# PowerDriver.net
KiCad netlist of a schematic drawn in Altium Designer
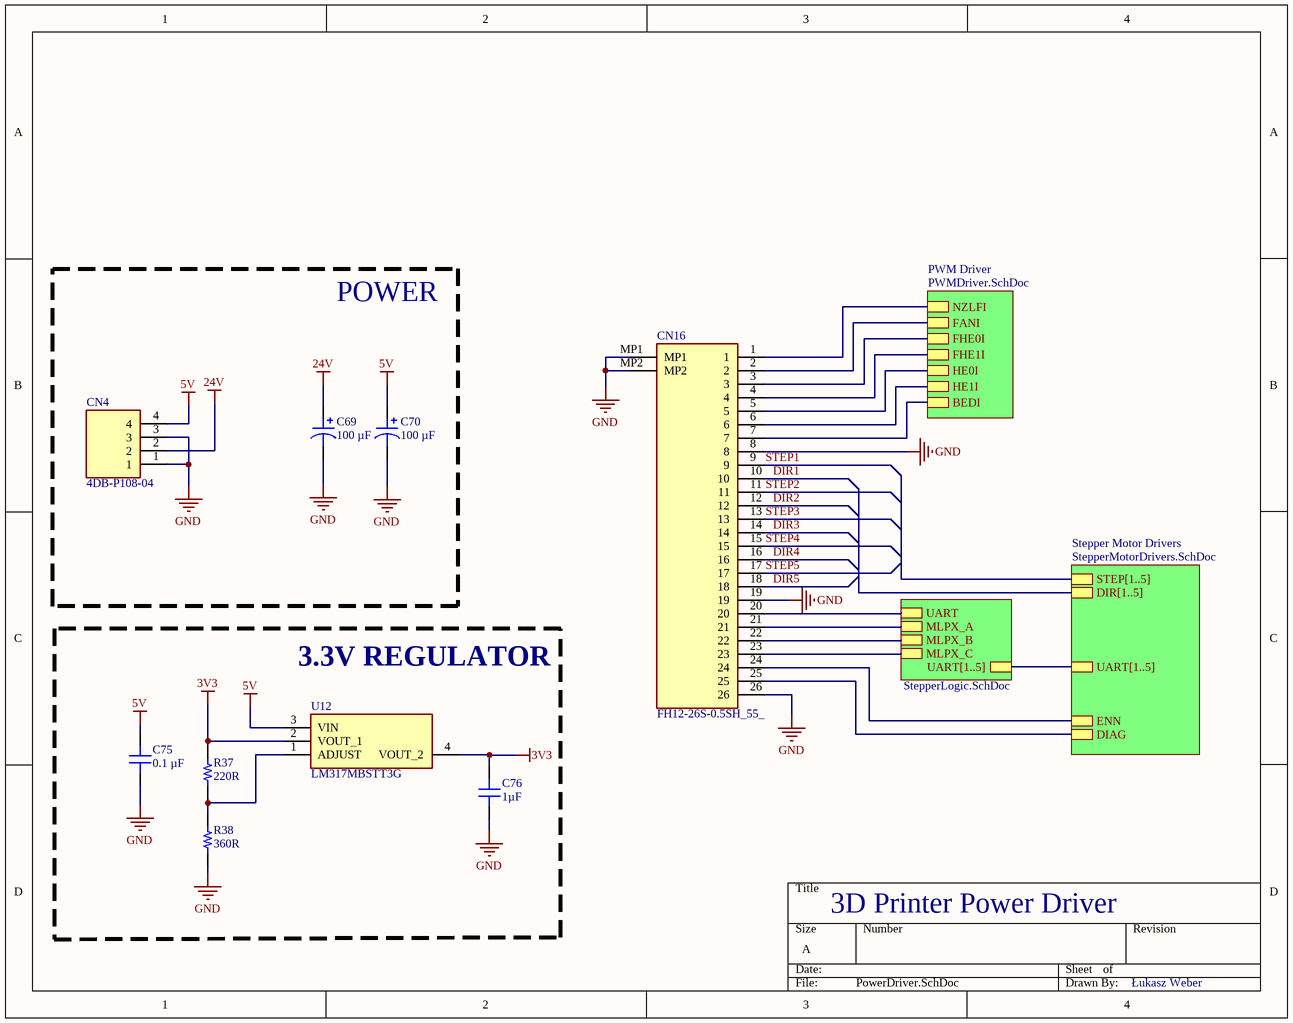
[diagram p0: PowerDriver.SchDoc]

(export (version "E")
  (design (tool "Eeschema 10.0.6"))
  (components
    (comp (ref "C69")
      (value "100 µF")
      (footprint "CAP ALSMD 6.6MM H7.7MM")
      (description "CAP ALUM 100UF 20% 25V SMD")
      (fields (field (name "PART NUMBER") "UWT1E101MCL1GS") (field (name "MANUFACTURER") "Nichicon"))
      (libsource (lib "Celestial Altium Library - altium_library") (part "Polarised Capacitor"))
    )
    (comp (ref "C70")
      (value "100 µF")
      (footprint "CAP ALSMD 6.6MM H7.7MM")
      (description "CAP ALUM 100UF 20% 25V SMD")
      (fields (field (name "PART NUMBER") "UWT1E101MCL1GS") (field (name "MANUFACTURER") "Nichicon"))
      (libsource (lib "Celestial Altium Library - altium_library") (part "Polarised Capacitor"))
    )
    (comp (ref "C75")
      (value "0.1 µF")
      (footprint "CAP 0603_1608")
      (description "CAP CER 0.1UF 100V X7R 0603")
      (fields
        (field (name "PART NUMBER") "0603B104K101CT")
        (field (name "MANUFACTURER") "Walsin Technology Corporation")
      )
      (libsource (lib "Celestial Altium Library - altium_library") (part "Capacitor"))
    )
    (comp (ref "C76")
      (value "1µF")
      (footprint "CAP 0603_1608")
      (description "CAP CER 1UF 16V X5R 0603")
      (fields (field (name "PART NUMBER") "0603YD105KAT4A") (field (name "MANUFACTURER") "AVX Corporation"))
      (libsource (lib "Celestial Altium Library - altium_library") (part "Capacitor"))
    )
    (comp (ref "CN4")
      (value "4DB-P108-04")
      (footprint "SamacSys:SHDR4W132P0X826_1X4_3467X1270X1346P")
      (description "Connector")
      (fields (field (name "MOUSER PART NUMBER") "571-214376676"))
      (libsource (lib "*") (part "4DB-P108-04"))
    )
    (comp (ref "CN16")
      (value "FH12-26S-0.5SH_55_")
      (footprint "Power Driver:FH1226S05SH55")
      (description "Connector")
      (fields
        (field (name "MANUFACTURER_PART_NUMBER") "FH12-26S-0.5SH(55)")
        (field (name "MOUSER PART NUMBER") "798-FH12-26S-0.5SH55")
      )
      (libsource (lib "SamacSys") (part "FH12-26S-0.5SH_55_"))
    )
    (comp (ref "R37")
      (value "220R")
      (footprint "RES 0603_1608")
      (description "RES SMD 240 OHM 1% 1/4W 0603")
      (fields (field (name "PART NUMBER") "RCS0603240RFKEA") (field (name "MANUFACTURER") "Vishay Dale"))
      (libsource (lib "Celestial Altium Library - altium_library") (part "Resistor"))
    )
    (comp (ref "R38")
      (value "360R")
      (footprint "RES 0603_1608")
      (description "RES SMD 2K OHM 5% 1/4W 0603")
      (fields (field (name "PART NUMBER") "ESR03EZPJ202") (field (name "MANUFACTURER") "Rohm Semiconductor"))
      (libsource (lib "Celestial Altium Library - altium_library") (part "Resistor"))
    )
    (comp (ref "U12")
      (value "LM317MBSTT3G")
      (footprint "Power Driver:SOT230P700X175-4N")
      (description "Integrated Circuit")
      (fields (field (name "MOUSER PART NUMBER") "863-LM317MBSTT3G"))
      (libsource (lib "*") (part "LM317MBSTT3G"))
    )
  )
  (nets
    (net (code "1") (name "/BEDI") (class "Default")
      (node (ref "CN16") (pin "7") (pinfunction "7_7") (pintype "passive"))
    )
    (net (code "2") (name "/DIAG") (class "Default")
      (node (ref "CN16") (pin "25") (pinfunction "25_25") (pintype "passive"))
    )
    (net (code "3") (name "/DIR1") (class "Default")
      (node (ref "CN16") (pin "10") (pinfunction "10_10") (pintype "passive"))
    )
    (net (code "4") (name "/DIR2") (class "Default")
      (node (ref "CN16") (pin "12") (pinfunction "12_12") (pintype "passive"))
    )
    (net (code "5") (name "/DIR3") (class "Default")
      (node (ref "CN16") (pin "14") (pinfunction "14_14") (pintype "passive"))
    )
    (net (code "6") (name "/DIR4") (class "Default")
      (node (ref "CN16") (pin "16") (pinfunction "16_16") (pintype "passive"))
    )
    (net (code "7") (name "/DIR5") (class "Default")
      (node (ref "CN16") (pin "18") (pinfunction "18_18") (pintype "passive"))
    )
    (net (code "9") (name "/ENN") (class "Default")
      (node (ref "CN16") (pin "24") (pinfunction "24_24") (pintype "passive"))
    )
    (net (code "10") (name "/FANI") (class "Default")
      (node (ref "CN16") (pin "2") (pinfunction "2_2") (pintype "passive"))
    )
    (net (code "11") (name "/FHE0I") (class "Default")
      (node (ref "CN16") (pin "3") (pinfunction "3_3") (pintype "passive"))
    )
    (net (code "12") (name "/FHE1I") (class "Default")
      (node (ref "CN16") (pin "4") (pinfunction "4_4") (pintype "passive"))
    )
    (net (code "13") (name "/HE0I") (class "Default")
      (node (ref "CN16") (pin "5") (pinfunction "5_5") (pintype "passive"))
    )
    (net (code "14") (name "/HE1I") (class "Default")
      (node (ref "CN16") (pin "6") (pinfunction "6_6") (pintype "passive"))
    )
    (net (code "15") (name "/MLPX_A") (class "Default")
      (node (ref "CN16") (pin "21") (pinfunction "21_21") (pintype "passive"))
    )
    (net (code "16") (name "/MLPX_B") (class "Default")
      (node (ref "CN16") (pin "22") (pinfunction "22_22") (pintype "passive"))
    )
    (net (code "17") (name "/MLPX_C") (class "Default")
      (node (ref "CN16") (pin "23") (pinfunction "23_23") (pintype "passive"))
    )
    (net (code "18") (name "/NZLFI") (class "Default")
      (node (ref "CN16") (pin "1") (pinfunction "1_1") (pintype "passive"))
    )
    (net (code "19") (name "/STEP1") (class "Default")
      (node (ref "CN16") (pin "9") (pinfunction "9_9") (pintype "passive"))
    )
    (net (code "20") (name "/STEP2") (class "Default")
      (node (ref "CN16") (pin "11") (pinfunction "11_11") (pintype "passive"))
    )
    (net (code "21") (name "/STEP3") (class "Default")
      (node (ref "CN16") (pin "13") (pinfunction "13_13") (pintype "passive"))
    )
    (net (code "22") (name "/STEP4") (class "Default")
      (node (ref "CN16") (pin "15") (pinfunction "15_15") (pintype "passive"))
    )
    (net (code "23") (name "/STEP5") (class "Default")
      (node (ref "CN16") (pin "17") (pinfunction "17_17") (pintype "passive"))
    )
    (net (code "25") (name "/UART") (class "Default")
      (node (ref "CN16") (pin "20") (pinfunction "20_20") (pintype "passive"))
    )
    (net (code "27") (name "3V3") (class "Default")
      (node (ref "C76") (pin "2") (pinfunction "2_2") (pintype "passive"))
      (node (ref "R37") (pin "2") (pinfunction "2_2") (pintype "passive"))
      (node (ref "U12") (pin "2") (pinfunction "VOUT_1_2") (pintype "passive"))
      (node (ref "U12") (pin "4") (pinfunction "VOUT_2_4") (pintype "passive"))
    )
    (net (code "28") (name "5V") (class "Default")
      (node (ref "C70") (pin "1") (pinfunction "1_1") (pintype "passive"))
      (node (ref "C75") (pin "2") (pinfunction "2_2") (pintype "passive"))
      (node (ref "CN4") (pin "4") (pinfunction "4_4") (pintype "passive"))
      (node (ref "U12") (pin "3") (pinfunction "VIN_3") (pintype "passive"))
    )
    (net (code "29") (name "24V") (class "Default")
      (node (ref "C69") (pin "1") (pinfunction "1_1") (pintype "passive"))
      (node (ref "CN4") (pin "2") (pinfunction "2_2") (pintype "passive"))
    )
    (net (code "30") (name "GND") (class "Default")
      (node (ref "C69") (pin "2") (pinfunction "2_2") (pintype "passive"))
      (node (ref "C70") (pin "2") (pinfunction "2_2") (pintype "passive"))
      (node (ref "C75") (pin "1") (pinfunction "1_1") (pintype "passive"))
      (node (ref "C76") (pin "1") (pinfunction "1_1") (pintype "passive"))
      (node (ref "CN16") (pin "19") (pinfunction "19_19") (pintype "passive"))
      (node (ref "CN16") (pin "26") (pinfunction "26_26") (pintype "passive"))
      (node (ref "CN16") (pin "8") (pinfunction "8_8") (pintype "passive"))
      (node (ref "CN16") (pin "MP1") (pinfunction "MP1_MP1") (pintype "passive"))
      (node (ref "CN16") (pin "MP2") (pinfunction "MP2_MP2") (pintype "passive"))
      (node (ref "CN4") (pin "1") (pinfunction "1_1") (pintype "passive"))
      (node (ref "CN4") (pin "3") (pinfunction "3_3") (pintype "passive"))
      (node (ref "R38") (pin "1") (pinfunction "1_1") (pintype "passive"))
    )
    (net (code "31") (name "Net-(U12-ADJUST)") (class "Default")
      (node (ref "R37") (pin "1") (pinfunction "1_1") (pintype "passive"))
      (node (ref "R38") (pin "2") (pinfunction "2_2") (pintype "passive"))
      (node (ref "U12") (pin "1") (pinfunction "ADJUST_1") (pintype "passive"))
    )
  )
)
